# XtalFilter.net
KiCad netlist of a schematic drawn in Altium Designer
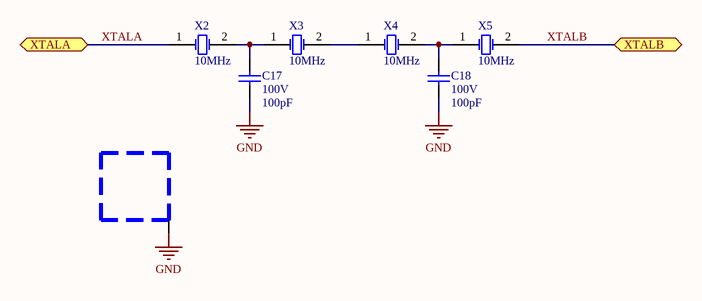
[diagram p0: XtalFilter.SchDoc]

(export (version "E")
  (design (tool "Eeschema 10.0.6"))
  (components
    (comp (ref "BL2")
      (value "Blindagem BPF")
      (footprint "SHIELD_26.5X26.5")
      (libsource (lib "Navarro") (part "Blindagem BPF"))
    )
    (comp (ref "C17")
      (value "100pF")
      (footprint "CC0603")
      (description "Capacitor (Semiconductor SIM Model)")
      (fields (field (name "TENSÃO") "100V") (field (name "Comment") "Capacitor Cerâmico"))
      (libsource (lib "NavarroCAP") (part "Cap 100pF 100V 0603 NP0"))
    )
    (comp (ref "C18")
      (value "100pF")
      (footprint "CC0603")
      (description "Capacitor (Semiconductor SIM Model)")
      (fields (field (name "TENSÃO") "100V") (field (name "Comment") "Capacitor Cerâmico"))
      (libsource (lib "NavarroCAP") (part "Cap 100pF 100V 0603 NP0"))
    )
    (comp (ref "X2")
      (value "10MHz")
      (footprint "HC/49US")
      (description "Crystal Oscillator")
      (libsource (lib "Navarro") (part "XTAL"))
    )
    (comp (ref "X3")
      (value "10MHz")
      (footprint "HC/49US")
      (description "Crystal Oscillator")
      (libsource (lib "Navarro") (part "XTAL"))
    )
    (comp (ref "X4")
      (value "10MHz")
      (footprint "HC/49US")
      (description "Crystal Oscillator")
      (libsource (lib "Navarro") (part "XTAL"))
    )
    (comp (ref "X5")
      (value "10MHz")
      (footprint "HC/49US")
      (description "Crystal Oscillator")
      (libsource (lib "Navarro") (part "XTAL"))
    )
  )
  (nets
    (net (code "1") (name "/XTALA") (class "Default")
      (node (ref "X2") (pin "1") (pinfunction "OSC1_1") (pintype "passive"))
    )
    (net (code "2") (name "/XTALB") (class "Default")
      (node (ref "X5") (pin "2") (pinfunction "OSC2_2") (pintype "passive"))
    )
    (net (code "3") (name "GND") (class "Default")
      (node (ref "BL2") (pin "1") (pinfunction "GND_1") (pintype "power_in"))
      (node (ref "C17") (pin "1") (pinfunction "1_1") (pintype "passive"))
      (node (ref "C18") (pin "1") (pinfunction "1_1") (pintype "passive"))
    )
    (net (code "4") (name "Net-(X2-OSC2)") (class "Default")
      (node (ref "C17") (pin "2") (pinfunction "2_2") (pintype "passive"))
      (node (ref "X2") (pin "2") (pinfunction "OSC2_2") (pintype "passive"))
      (node (ref "X3") (pin "1") (pinfunction "OSC1_1") (pintype "passive"))
    )
    (net (code "5") (name "Net-(X3-OSC2)") (class "Default")
      (node (ref "X3") (pin "2") (pinfunction "OSC2_2") (pintype "passive"))
      (node (ref "X4") (pin "1") (pinfunction "OSC1_1") (pintype "passive"))
    )
    (net (code "6") (name "Net-(X4-OSC2)") (class "Default")
      (node (ref "C18") (pin "2") (pinfunction "2_2") (pintype "passive"))
      (node (ref "X4") (pin "2") (pinfunction "OSC2_2") (pintype "passive"))
      (node (ref "X5") (pin "1") (pinfunction "OSC1_1") (pintype "passive"))
    )
  )
)
